# Sintetizador_BA.net
KiCad netlist of a schematic drawn in Altium Designer
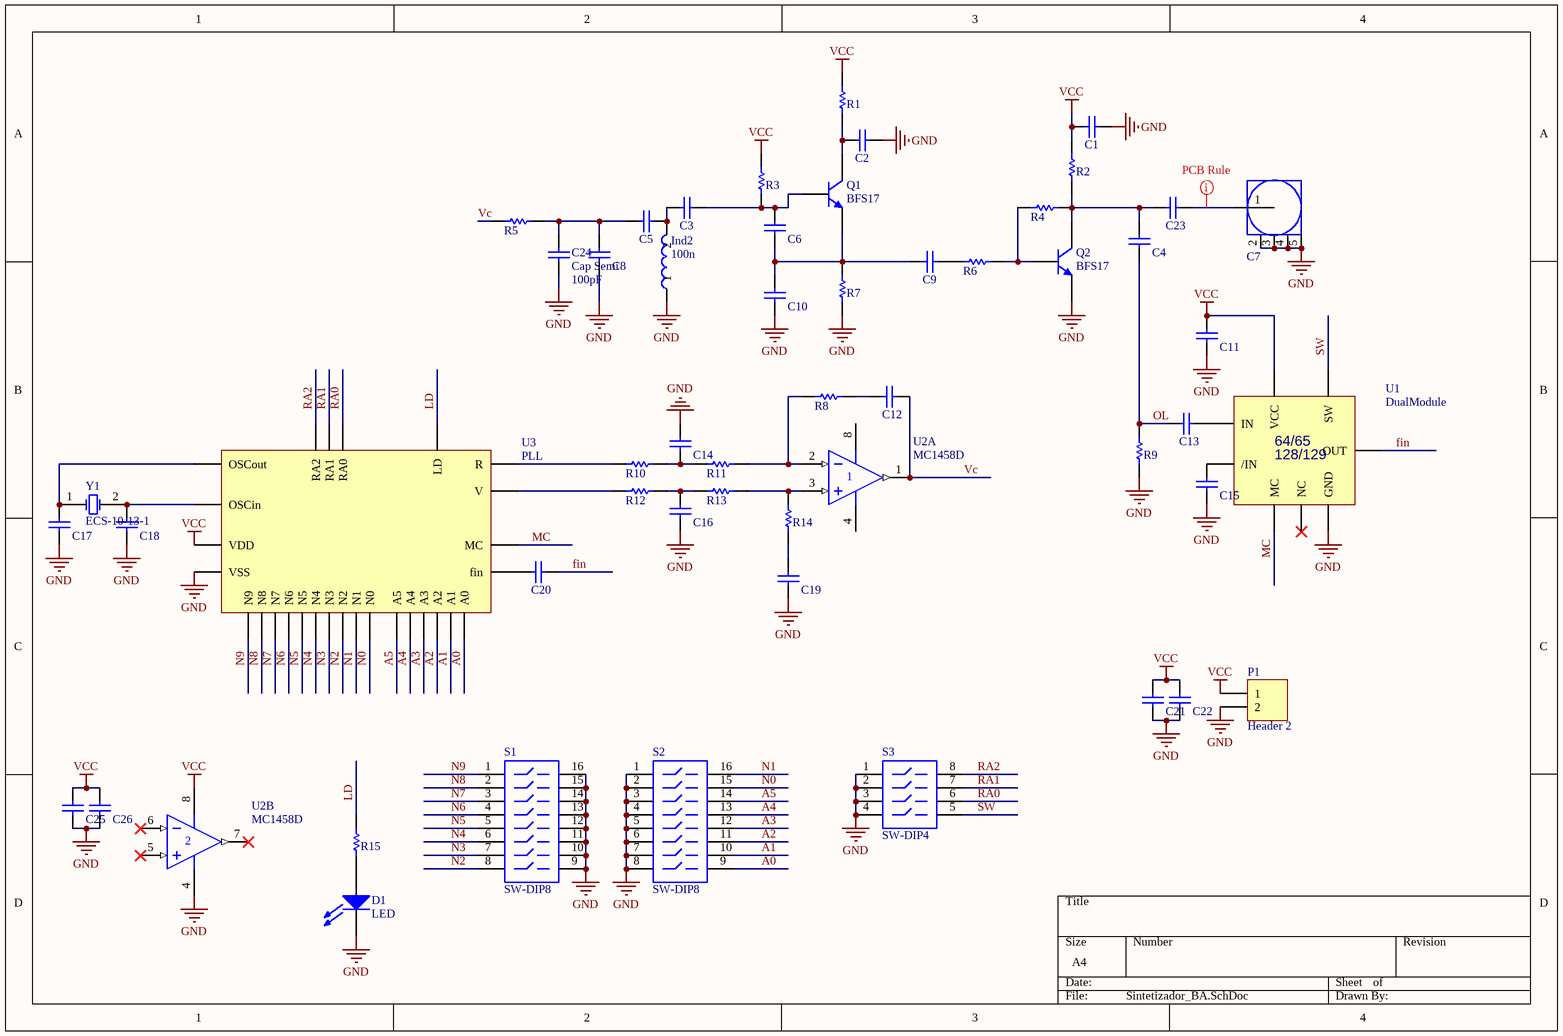
[diagram p0: Sintetizador_BA.SchDoc]

(export (version "E")
  (design (tool "Eeschema 10.0.6"))
  (components
    (comp (ref "C1") (value "Capacitor") (footprint "0805_CAP") (libsource (lib "epf") (part "Cap")))
    (comp (ref "C2") (value "Capacitor") (footprint "0805_CAP") (libsource (lib "epf") (part "Cap")))
    (comp (ref "C3") (value "Capacitor") (footprint "0805_CAP") (libsource (lib "epf") (part "Cap")))
    (comp (ref "C4") (value "Capacitor") (footprint "0805_CAP") (libsource (lib "epf") (part "Cap")))
    (comp (ref "C5") (value "Capacitor") (footprint "0805_CAP") (libsource (lib "epf") (part "Cap")))
    (comp (ref "C6") (value "Capacitor") (footprint "0805_CAP") (libsource (lib "epf") (part "Cap")))
    (comp (ref "C7") (value "SMA") (footprint "SMAL2") (libsource (lib "epf") (part "SMA")))
    (comp (ref "C8") (value "Capacitor") (footprint "0805_CAP") (libsource (lib "epf") (part "Cap")))
    (comp (ref "C9") (value "Capacitor") (footprint "0805_CAP") (libsource (lib "epf") (part "Cap")))
    (comp (ref "C10") (value "Capacitor") (footprint "0805_CAP") (libsource (lib "epf") (part "Cap")))
    (comp (ref "C11") (value "Capacitor") (footprint "0805_CAP") (libsource (lib "epf") (part "Cap")))
    (comp (ref "C12") (value "Capacitor") (footprint "0805_CAP") (libsource (lib "epf") (part "Cap")))
    (comp (ref "C13") (value "Capacitor") (footprint "0805_CAP") (libsource (lib "epf") (part "Cap")))
    (comp (ref "C14") (value "Capacitor") (footprint "0805_CAP") (libsource (lib "epf") (part "Cap")))
    (comp (ref "C15") (value "Capacitor") (footprint "0805_CAP") (libsource (lib "epf") (part "Cap")))
    (comp (ref "C16") (value "Capacitor") (footprint "0805_CAP") (libsource (lib "epf") (part "Cap")))
    (comp (ref "C17") (value "Capacitor") (footprint "0805_CAP") (libsource (lib "epf") (part "Cap")))
    (comp (ref "C18") (value "Capacitor") (footprint "0805_CAP") (libsource (lib "epf") (part "Cap")))
    (comp (ref "C19") (value "Capacitor") (footprint "0805_CAP") (libsource (lib "epf") (part "Cap")))
    (comp (ref "C20") (value "Capacitor") (footprint "0805_CAP") (libsource (lib "epf") (part "Cap")))
    (comp (ref "C21") (value "Capacitor") (footprint "0805_CAP") (libsource (lib "epf") (part "Cap")))
    (comp (ref "C22") (value "Capacitor") (footprint "0805_CAP") (libsource (lib "epf") (part "Cap")))
    (comp (ref "C23") (value "Capacitor") (footprint "0805_CAP") (libsource (lib "epf") (part "Cap")))
    (comp (ref "C24")
      (value "Cap Semi")
      (footprint "C1206")
      (description "Capacitor (Semiconductor SIM Model)")
      (fields (field (name "ALTIUM_VALUE") "100pF") (field (name "PUBLISHER") "Altium Limited"))
      (libsource (lib "Miscellaneous Devices") (part "Cap Semi"))
    )
    (comp (ref "C25") (value "Capacitor") (footprint "0805_CAP") (libsource (lib "epf") (part "Cap")))
    (comp (ref "C26") (value "Capacitor") (footprint "0805_CAP") (libsource (lib "epf") (part "Cap")))
    (comp (ref "D1") (value "LED") (footprint "PLCC-2Rojo") (libsource (lib "epf") (part "LED1")))
    (comp (ref "Ind2")
      (value "Ind2")
      (footprint "Ind_4mm")
      (fields (field (name "VALOR") "100n"))
      (libsource (lib "epf") (part "Ind2"))
    )
    (comp (ref "P1")
      (value "Header 2")
      (footprint "HDR1X2")
      (description "Header, 2-Pin")
      (fields (field (name "PUBLISHER") "Altium Limited"))
      (libsource (lib "Miscellaneous Connectors") (part "Header 2"))
    )
    (comp (ref "Q1")
      (value "BFS17")
      (footprint "SOT-23")
      (description "NPN 1 GHz Wideband Transistor")
      (fields (field (name "PUBLISHER") "Altium Limited"))
      (libsource (lib "Philips Discrete BJT - RF Transistor") (part "BFS17"))
    )
    (comp (ref "Q2")
      (value "BFS17")
      (footprint "SOT23_N")
      (description "NPN 1 GHz Wideband Transistor")
      (fields (field (name "PUBLISHER") "Altium Limited"))
      (libsource (lib "Philips Discrete BJT - RF Transistor") (part "BFS17"))
    )
    (comp (ref "R1") (value "Resistor") (footprint "0805_RES") (libsource (lib "epf") (part "Res")))
    (comp (ref "R2") (value "Resistor") (footprint "0805_RES") (libsource (lib "epf") (part "Res")))
    (comp (ref "R3") (value "Resistor") (footprint "0805_RES") (libsource (lib "epf") (part "Res")))
    (comp (ref "R4") (value "Resistor") (footprint "0805_RES") (libsource (lib "epf") (part "Res")))
    (comp (ref "R5") (value "Resistor") (footprint "0805_RES") (libsource (lib "epf") (part "Res")))
    (comp (ref "R6") (value "Resistor") (footprint "0805_RES") (libsource (lib "epf") (part "Res")))
    (comp (ref "R7") (value "Resistor") (footprint "0805_RES") (libsource (lib "epf") (part "Res")))
    (comp (ref "R8") (value "Resistor") (footprint "0805_RES") (libsource (lib "epf") (part "Res")))
    (comp (ref "R9") (value "Resistor") (footprint "0805_RES") (libsource (lib "epf") (part "Res")))
    (comp (ref "R10") (value "Resistor") (footprint "0805_RES") (libsource (lib "epf") (part "Res")))
    (comp (ref "R11") (value "Resistor") (footprint "0805_RES") (libsource (lib "epf") (part "Res")))
    (comp (ref "R12") (value "Resistor") (footprint "0805_RES") (libsource (lib "epf") (part "Res")))
    (comp (ref "R13") (value "Resistor") (footprint "0805_RES") (libsource (lib "epf") (part "Res")))
    (comp (ref "R14") (value "Resistor") (footprint "0805_RES") (libsource (lib "epf") (part "Res")))
    (comp (ref "R15") (value "Resistor") (footprint "0805_RES") (libsource (lib "epf") (part "Res")))
    (comp (ref "S1")
      (value "SW-DIP8")
      (footprint "DIP-16-KEY")
      (description "4009 Series DIP Switch, Raised actuator")
      (fields (field (name "PUBLISHER") "Altium Limited"))
      (libsource (lib "Miscellaneous Devices") (part "SW-DIP8"))
    )
    (comp (ref "S2")
      (value "SW-DIP8")
      (footprint "DIP-16-KEY")
      (description "4009 Series DIP Switch, Raised actuator")
      (fields (field (name "PUBLISHER") "Altium Limited"))
      (libsource (lib "Miscellaneous Devices") (part "SW-DIP8"))
    )
    (comp (ref "S3")
      (value "SW-DIP4")
      (footprint "DIP-8")
      (description "DIP Switch")
      (fields (field (name "PUBLISHER") "Altium Limited"))
      (libsource (lib "Miscellaneous Devices") (part "SW-DIP4"))
    )
    (comp (ref "U1") (value "DualModule") (footprint "SO-8_2") (libsource (lib "epf") (part "MC12054ASD")))
    (comp (ref "U2")
      (value "MC1458D")
      (footprint "751-05_N")
      (description "Dual Operational Amplifier, Internally Compensated")
      (fields (field (name "PUBLISHER") "Altium Limited"))
      (libsource (lib "Motorola Amplifier Operational Amplifier") (part "MC1458D"))
    )
    (comp (ref "U3")
      (value "PLL")
      (footprint "SOG28")
      (description "PLL paralelo doble modulo")
      (libsource (lib "epf") (part "MC145152P2"))
    )
    (comp (ref "Y1")
      (value "ECS-10-13-1")
      (footprint "HC-49U")
      (description "Crystal Oscillator")
      (fields (field (name "PUBLISHER") "Altium Limited"))
      (libsource (lib "ECS Crystal Oscillator") (part "ECS-10-13-1"))
    )
  )
  (nets
    (net (code "1") (name "/A0") (class "Default")
      (node (ref "S2") (pin "9") (pinfunction "9_9") (pintype "passive"))
      (node (ref "U3") (pin "23") (pinfunction "A0_23") (pintype "passive"))
    )
    (net (code "2") (name "/A1") (class "Default")
      (node (ref "S2") (pin "10") (pinfunction "10_10") (pintype "passive"))
      (node (ref "U3") (pin "21") (pinfunction "A1_21") (pintype "passive"))
    )
    (net (code "3") (name "/A2") (class "Default")
      (node (ref "S2") (pin "11") (pinfunction "11_11") (pintype "passive"))
      (node (ref "U3") (pin "22") (pinfunction "A2_22") (pintype "passive"))
    )
    (net (code "4") (name "/A3") (class "Default")
      (node (ref "S2") (pin "12") (pinfunction "12_12") (pintype "passive"))
      (node (ref "U3") (pin "24") (pinfunction "A3_24") (pintype "passive"))
    )
    (net (code "5") (name "/A4") (class "Default")
      (node (ref "S2") (pin "13") (pinfunction "13_13") (pintype "passive"))
      (node (ref "U3") (pin "25") (pinfunction "A4_25") (pintype "passive"))
    )
    (net (code "6") (name "/A5") (class "Default")
      (node (ref "S2") (pin "14") (pinfunction "14_14") (pintype "passive"))
      (node (ref "U3") (pin "10") (pinfunction "A5_10") (pintype "passive"))
    )
    (net (code "7") (name "/LD") (class "Default")
      (node (ref "R15") (pin "1") (pinfunction "1_1") (pintype "passive"))
      (node (ref "U3") (pin "28") (pinfunction "LD_28") (pintype "passive"))
    )
    (net (code "8") (name "/MC") (class "Default")
      (node (ref "U1") (pin "6") (pinfunction "MC_6") (pintype "passive"))
      (node (ref "U3") (pin "9") (pinfunction "MC_9") (pintype "passive"))
    )
    (net (code "9") (name "/N0") (class "Default")
      (node (ref "S2") (pin "15") (pinfunction "15_15") (pintype "passive"))
      (node (ref "U3") (pin "11") (pinfunction "N0_11") (pintype "passive"))
    )
    (net (code "10") (name "/N1") (class "Default")
      (node (ref "S2") (pin "16") (pinfunction "16_16") (pintype "passive"))
      (node (ref "U3") (pin "12") (pinfunction "N1_12") (pintype "passive"))
    )
    (net (code "11") (name "/N2") (class "Default")
      (node (ref "S1") (pin "8") (pinfunction "8_8") (pintype "passive"))
      (node (ref "U3") (pin "13") (pinfunction "N2_13") (pintype "passive"))
    )
    (net (code "12") (name "/N3") (class "Default")
      (node (ref "S1") (pin "7") (pinfunction "7_7") (pintype "passive"))
      (node (ref "U3") (pin "14") (pinfunction "N3_14") (pintype "passive"))
    )
    (net (code "13") (name "/N4") (class "Default")
      (node (ref "S1") (pin "6") (pinfunction "6_6") (pintype "passive"))
      (node (ref "U3") (pin "15") (pinfunction "N4_15") (pintype "passive"))
    )
    (net (code "14") (name "/N5") (class "Default")
      (node (ref "S1") (pin "5") (pinfunction "5_5") (pintype "passive"))
      (node (ref "U3") (pin "16") (pinfunction "N5_16") (pintype "passive"))
    )
    (net (code "15") (name "/N6") (class "Default")
      (node (ref "S1") (pin "4") (pinfunction "4_4") (pintype "passive"))
      (node (ref "U3") (pin "17") (pinfunction "N6_17") (pintype "passive"))
    )
    (net (code "16") (name "/N7") (class "Default")
      (node (ref "S1") (pin "3") (pinfunction "3_3") (pintype "passive"))
      (node (ref "U3") (pin "18") (pinfunction "N7_18") (pintype "passive"))
    )
    (net (code "17") (name "/N8") (class "Default")
      (node (ref "S1") (pin "2") (pinfunction "2_2") (pintype "passive"))
      (node (ref "U3") (pin "19") (pinfunction "N8_19") (pintype "passive"))
    )
    (net (code "18") (name "/N9") (class "Default")
      (node (ref "S1") (pin "1") (pinfunction "1_1") (pintype "passive"))
      (node (ref "U3") (pin "20") (pinfunction "N9_20") (pintype "passive"))
    )
    (net (code "19") (name "/OL") (class "Default")
      (node (ref "C13") (pin "2") (pinfunction "2_2") (pintype "passive"))
      (node (ref "C4") (pin "2") (pinfunction "2_2") (pintype "passive"))
      (node (ref "R9") (pin "1") (pinfunction "1_1") (pintype "passive"))
    )
    (net (code "20") (name "/RA0") (class "Default")
      (node (ref "S3") (pin "6") (pinfunction "6_6") (pintype "passive"))
      (node (ref "U3") (pin "4") (pinfunction "RA0_4") (pintype "passive"))
    )
    (net (code "21") (name "/RA1") (class "Default")
      (node (ref "S3") (pin "7") (pinfunction "7_7") (pintype "passive"))
      (node (ref "U3") (pin "5") (pinfunction "RA1_5") (pintype "passive"))
    )
    (net (code "22") (name "/RA2") (class "Default")
      (node (ref "S3") (pin "8") (pinfunction "8_8") (pintype "passive"))
      (node (ref "U3") (pin "6") (pinfunction "RA2_6") (pintype "passive"))
    )
    (net (code "23") (name "/SW") (class "Default")
      (node (ref "S3") (pin "5") (pinfunction "5_5") (pintype "passive"))
      (node (ref "U1") (pin "3") (pinfunction "SW_3") (pintype "passive"))
    )
    (net (code "24") (name "/Vc") (class "Default")
      (node (ref "C12") (pin "1") (pinfunction "1_1") (pintype "passive"))
      (node (ref "R5") (pin "1") (pinfunction "1_1") (pintype "passive"))
      (node (ref "U2") (pin "1") (pinfunction "OUT_1") (pintype "output"))
    )
    (net (code "25") (name "/fin") (class "Default")
      (node (ref "C20") (pin "1") (pinfunction "1_1") (pintype "passive"))
      (node (ref "U1") (pin "4") (pinfunction "OUT_4") (pintype "passive"))
    )
    (net (code "26") (name "GND") (class "Default")
      (node (ref "C1") (pin "1") (pinfunction "1_1") (pintype "passive"))
      (node (ref "C10") (pin "2") (pinfunction "2_2") (pintype "passive"))
      (node (ref "C11") (pin "2") (pinfunction "2_2") (pintype "passive"))
      (node (ref "C14") (pin "2") (pinfunction "2_2") (pintype "passive"))
      (node (ref "C15") (pin "2") (pinfunction "2_2") (pintype "passive"))
      (node (ref "C16") (pin "1") (pinfunction "1_1") (pintype "passive"))
      (node (ref "C17") (pin "1") (pinfunction "1_1") (pintype "passive"))
      (node (ref "C18") (pin "1") (pinfunction "1_1") (pintype "passive"))
      (node (ref "C19") (pin "1") (pinfunction "1_1") (pintype "passive"))
      (node (ref "C2") (pin "1") (pinfunction "1_1") (pintype "passive"))
      (node (ref "C21") (pin "1") (pinfunction "1_1") (pintype "passive"))
      (node (ref "C22") (pin "1") (pinfunction "1_1") (pintype "passive"))
      (node (ref "C24") (pin "2") (pinfunction "2_2") (pintype "passive"))
      (node (ref "C25") (pin "1") (pinfunction "1_1") (pintype "passive"))
      (node (ref "C26") (pin "1") (pinfunction "1_1") (pintype "passive"))
      (node (ref "C7") (pin "2") (pinfunction "GND_2") (pintype "passive"))
      (node (ref "C7") (pin "3") (pinfunction "GND_3") (pintype "passive"))
      (node (ref "C7") (pin "4") (pinfunction "GND_4") (pintype "passive"))
      (node (ref "C7") (pin "5") (pinfunction "GND_5") (pintype "passive"))
      (node (ref "C8") (pin "1") (pinfunction "1_1") (pintype "passive"))
      (node (ref "D1") (pin "2") (pinfunction "K_2") (pintype "passive"))
      (node (ref "Ind2") (pin "1") (pinfunction "1_1") (pintype "passive"))
      (node (ref "P1") (pin "2") (pinfunction "2_2") (pintype "passive"))
      (node (ref "Q2") (pin "2") (pinfunction "E_2") (pintype "passive"))
      (node (ref "R7") (pin "1") (pinfunction "1_1") (pintype "passive"))
      (node (ref "R9") (pin "2") (pinfunction "2_2") (pintype "passive"))
      (node (ref "S1") (pin "10") (pinfunction "10_10") (pintype "passive"))
      (node (ref "S1") (pin "11") (pinfunction "11_11") (pintype "passive"))
      (node (ref "S1") (pin "12") (pinfunction "12_12") (pintype "passive"))
      (node (ref "S1") (pin "13") (pinfunction "13_13") (pintype "passive"))
      (node (ref "S1") (pin "14") (pinfunction "14_14") (pintype "passive"))
      (node (ref "S1") (pin "15") (pinfunction "15_15") (pintype "passive"))
      (node (ref "S1") (pin "16") (pinfunction "16_16") (pintype "passive"))
      (node (ref "S1") (pin "9") (pinfunction "9_9") (pintype "passive"))
      (node (ref "S2") (pin "1") (pinfunction "1_1") (pintype "passive"))
      (node (ref "S2") (pin "2") (pinfunction "2_2") (pintype "passive"))
      (node (ref "S2") (pin "3") (pinfunction "3_3") (pintype "passive"))
      (node (ref "S2") (pin "4") (pinfunction "4_4") (pintype "passive"))
      (node (ref "S2") (pin "5") (pinfunction "5_5") (pintype "passive"))
      (node (ref "S2") (pin "6") (pinfunction "6_6") (pintype "passive"))
      (node (ref "S2") (pin "7") (pinfunction "7_7") (pintype "passive"))
      (node (ref "S2") (pin "8") (pinfunction "8_8") (pintype "passive"))
      (node (ref "S3") (pin "1") (pinfunction "1_1") (pintype "passive"))
      (node (ref "S3") (pin "2") (pinfunction "2_2") (pintype "passive"))
      (node (ref "S3") (pin "3") (pinfunction "3_3") (pintype "passive"))
      (node (ref "S3") (pin "4") (pinfunction "4_4") (pintype "passive"))
      (node (ref "U1") (pin "5") (pinfunction "GND_5") (pintype "passive"))
      (node (ref "U2") (pin "4") (pinfunction "V-_4") (pintype "power_in"))
      (node (ref "U3") (pin "2") (pinfunction "VSS_2") (pintype "passive"))
    )
    (net (code "27") (name "Net-(C3-Pad2)") (class "Default")
      (node (ref "C3") (pin "2") (pinfunction "2_2") (pintype "passive"))
      (node (ref "C5") (pin "1") (pinfunction "1_1") (pintype "passive"))
      (node (ref "Ind2") (pin "2") (pinfunction "2_2") (pintype "passive"))
    )
    (net (code "28") (name "Net-(C7-RF)") (class "Default")
      (node (ref "C23") (pin "1") (pinfunction "1_1") (pintype "passive"))
      (node (ref "C7") (pin "1") (pinfunction "RF_1") (pintype "passive"))
    )
    (net (code "29") (name "Net-(C9-Pad2)") (class "Default")
      (node (ref "C9") (pin "2") (pinfunction "2_2") (pintype "passive"))
      (node (ref "R6") (pin "2") (pinfunction "2_2") (pintype "passive"))
    )
    (net (code "30") (name "Net-(C12-Pad2)") (class "Default")
      (node (ref "C12") (pin "2") (pinfunction "2_2") (pintype "passive"))
      (node (ref "R8") (pin "1") (pinfunction "1_1") (pintype "passive"))
    )
    (net (code "31") (name "Net-(C14-Pad1)") (class "Default")
      (node (ref "C14") (pin "1") (pinfunction "1_1") (pintype "passive"))
      (node (ref "R10") (pin "2") (pinfunction "2_2") (pintype "passive"))
      (node (ref "R11") (pin "1") (pinfunction "1_1") (pintype "passive"))
    )
    (net (code "32") (name "Net-(C16-Pad2)") (class "Default")
      (node (ref "C16") (pin "2") (pinfunction "2_2") (pintype "passive"))
      (node (ref "R12") (pin "2") (pinfunction "2_2") (pintype "passive"))
      (node (ref "R13") (pin "1") (pinfunction "1_1") (pintype "passive"))
    )
    (net (code "33") (name "Net-(C19-Pad2)") (class "Default")
      (node (ref "C19") (pin "2") (pinfunction "2_2") (pintype "passive"))
      (node (ref "R14") (pin "1") (pinfunction "1_1") (pintype "passive"))
    )
    (net (code "34") (name "Net-(C24-Pad1)") (class "Default")
      (node (ref "C24") (pin "1") (pinfunction "1_1") (pintype "passive"))
      (node (ref "C5") (pin "2") (pinfunction "2_2") (pintype "passive"))
      (node (ref "C8") (pin "2") (pinfunction "2_2") (pintype "passive"))
      (node (ref "R5") (pin "2") (pinfunction "2_2") (pintype "passive"))
    )
    (net (code "35") (name "Net-(D1-A)") (class "Default")
      (node (ref "D1") (pin "1") (pinfunction "A_1") (pintype "passive"))
      (node (ref "R15") (pin "2") (pinfunction "2_2") (pintype "passive"))
    )
    (net (code "36") (name "Net-(Q1-B)") (class "Default")
      (node (ref "C3") (pin "1") (pinfunction "1_1") (pintype "passive"))
      (node (ref "C6") (pin "1") (pinfunction "1_1") (pintype "passive"))
      (node (ref "Q1") (pin "1") (pinfunction "B_1") (pintype "passive"))
      (node (ref "R3") (pin "2") (pinfunction "2_2") (pintype "passive"))
    )
    (net (code "37") (name "Net-(Q1-C)") (class "Default")
      (node (ref "C2") (pin "2") (pinfunction "2_2") (pintype "passive"))
      (node (ref "Q1") (pin "3") (pinfunction "C_3") (pintype "passive"))
      (node (ref "R1") (pin "2") (pinfunction "2_2") (pintype "passive"))
    )
    (net (code "38") (name "Net-(Q1-E)") (class "Default")
      (node (ref "C10") (pin "1") (pinfunction "1_1") (pintype "passive"))
      (node (ref "C6") (pin "2") (pinfunction "2_2") (pintype "passive"))
      (node (ref "C9") (pin "1") (pinfunction "1_1") (pintype "passive"))
      (node (ref "Q1") (pin "2") (pinfunction "E_2") (pintype "passive"))
      (node (ref "R7") (pin "2") (pinfunction "2_2") (pintype "passive"))
    )
    (net (code "39") (name "Net-(Q2-B)") (class "Default")
      (node (ref "Q2") (pin "1") (pinfunction "B_1") (pintype "passive"))
      (node (ref "R4") (pin "2") (pinfunction "2_2") (pintype "passive"))
      (node (ref "R6") (pin "1") (pinfunction "1_1") (pintype "passive"))
    )
    (net (code "40") (name "Net-(Q2-C)") (class "Default")
      (node (ref "C23") (pin "2") (pinfunction "2_2") (pintype "passive"))
      (node (ref "C4") (pin "1") (pinfunction "1_1") (pintype "passive"))
      (node (ref "Q2") (pin "3") (pinfunction "C_3") (pintype "passive"))
      (node (ref "R2") (pin "2") (pinfunction "2_2") (pintype "passive"))
      (node (ref "R4") (pin "1") (pinfunction "1_1") (pintype "passive"))
    )
    (net (code "41") (name "Net-(U1-IN)") (class "Default")
      (node (ref "C13") (pin "1") (pinfunction "1_1") (pintype "passive"))
      (node (ref "U1") (pin "1") (pinfunction "IN_1") (pintype "passive"))
    )
    (net (code "42") (name "Net-(U1-{slash}IN)") (class "Default")
      (node (ref "C15") (pin "1") (pinfunction "1_1") (pintype "passive"))
      (node (ref "U1") (pin "8") (pinfunction "/IN_8") (pintype "passive"))
    )
    (net (code "43") (name "Net-(U2A-IN+)") (class "Default")
      (node (ref "R13") (pin "2") (pinfunction "2_2") (pintype "passive"))
      (node (ref "R14") (pin "2") (pinfunction "2_2") (pintype "passive"))
      (node (ref "U2") (pin "3") (pinfunction "IN+_3") (pintype "input"))
    )
    (net (code "44") (name "Net-(U2A-IN-)") (class "Default")
      (node (ref "R11") (pin "2") (pinfunction "2_2") (pintype "passive"))
      (node (ref "R8") (pin "2") (pinfunction "2_2") (pintype "passive"))
      (node (ref "U2") (pin "2") (pinfunction "IN-_2") (pintype "input"))
    )
    (net (code "45") (name "Net-(U3-OSCin)") (class "Default")
      (node (ref "C18") (pin "2") (pinfunction "2_2") (pintype "passive"))
      (node (ref "U3") (pin "27") (pinfunction "OSCin_27") (pintype "passive"))
      (node (ref "Y1") (pin "2") (pinfunction "OSC2_2") (pintype "passive"))
    )
    (net (code "46") (name "Net-(U3-OSCout)") (class "Default")
      (node (ref "C17") (pin "2") (pinfunction "2_2") (pintype "passive"))
      (node (ref "U3") (pin "26") (pinfunction "OSCout_26") (pintype "passive"))
      (node (ref "Y1") (pin "1") (pinfunction "OSC1_1") (pintype "passive"))
    )
    (net (code "47") (name "Net-(U3-R)") (class "Default")
      (node (ref "R10") (pin "1") (pinfunction "1_1") (pintype "passive"))
      (node (ref "U3") (pin "7") (pinfunction "R_7") (pintype "passive"))
    )
    (net (code "48") (name "Net-(U3-V)") (class "Default")
      (node (ref "R12") (pin "1") (pinfunction "1_1") (pintype "passive"))
      (node (ref "U3") (pin "8") (pinfunction "V_8") (pintype "passive"))
    )
    (net (code "49") (name "Net-(U3-fin)") (class "Default")
      (node (ref "C20") (pin "2") (pinfunction "2_2") (pintype "passive"))
      (node (ref "U3") (pin "1") (pinfunction "fin_1") (pintype "passive"))
    )
    (net (code "50") (name "VCC") (class "Default")
      (node (ref "C1") (pin "2") (pinfunction "2_2") (pintype "passive"))
      (node (ref "C11") (pin "1") (pinfunction "1_1") (pintype "passive"))
      (node (ref "C21") (pin "2") (pinfunction "2_2") (pintype "passive"))
      (node (ref "C22") (pin "2") (pinfunction "2_2") (pintype "passive"))
      (node (ref "C25") (pin "2") (pinfunction "2_2") (pintype "passive"))
      (node (ref "C26") (pin "2") (pinfunction "2_2") (pintype "passive"))
      (node (ref "P1") (pin "1") (pinfunction "1_1") (pintype "passive"))
      (node (ref "R1") (pin "1") (pinfunction "1_1") (pintype "passive"))
      (node (ref "R2") (pin "1") (pinfunction "1_1") (pintype "passive"))
      (node (ref "R3") (pin "1") (pinfunction "1_1") (pintype "passive"))
      (node (ref "U1") (pin "2") (pinfunction "VCC_2") (pintype "passive"))
      (node (ref "U2") (pin "8") (pinfunction "V+_8") (pintype "power_in"))
      (node (ref "U3") (pin "3") (pinfunction "VDD_3") (pintype "passive"))
    )
    (net (code "51") (name "unconnected-(U1-NC-Pad7)") (class "Default")
      (node (ref "U1") (pin "7") (pinfunction "NC_7") (pintype "passive+no_connect"))
    )
    (net (code "52") (name "unconnected-(U2A-V+-Pad8)") (class "Default")
      (node (ref "U2") (pin "8") (pinfunction "V+_8") (pintype "power_in"))
    )
    (net (code "53") (name "unconnected-(U2A-V--Pad4)") (class "Default")
      (node (ref "U2") (pin "4") (pinfunction "V-_4") (pintype "power_in"))
    )
    (net (code "54") (name "unconnected-(U2B-IN+-Pad5)") (class "Default")
      (node (ref "U2") (pin "5") (pinfunction "IN+_5") (pintype "input+no_connect"))
    )
    (net (code "55") (name "unconnected-(U2B-IN--Pad6)") (class "Default")
      (node (ref "U2") (pin "6") (pinfunction "IN-_6") (pintype "input+no_connect"))
    )
    (net (code "56") (name "unconnected-(U2B-OUT-Pad7)") (class "Default")
      (node (ref "U2") (pin "7") (pinfunction "OUT_7") (pintype "output+no_connect"))
    )
  )
)
